# 2um_Homodyne.net
KiCad netlist of a schematic drawn in Altium Designer
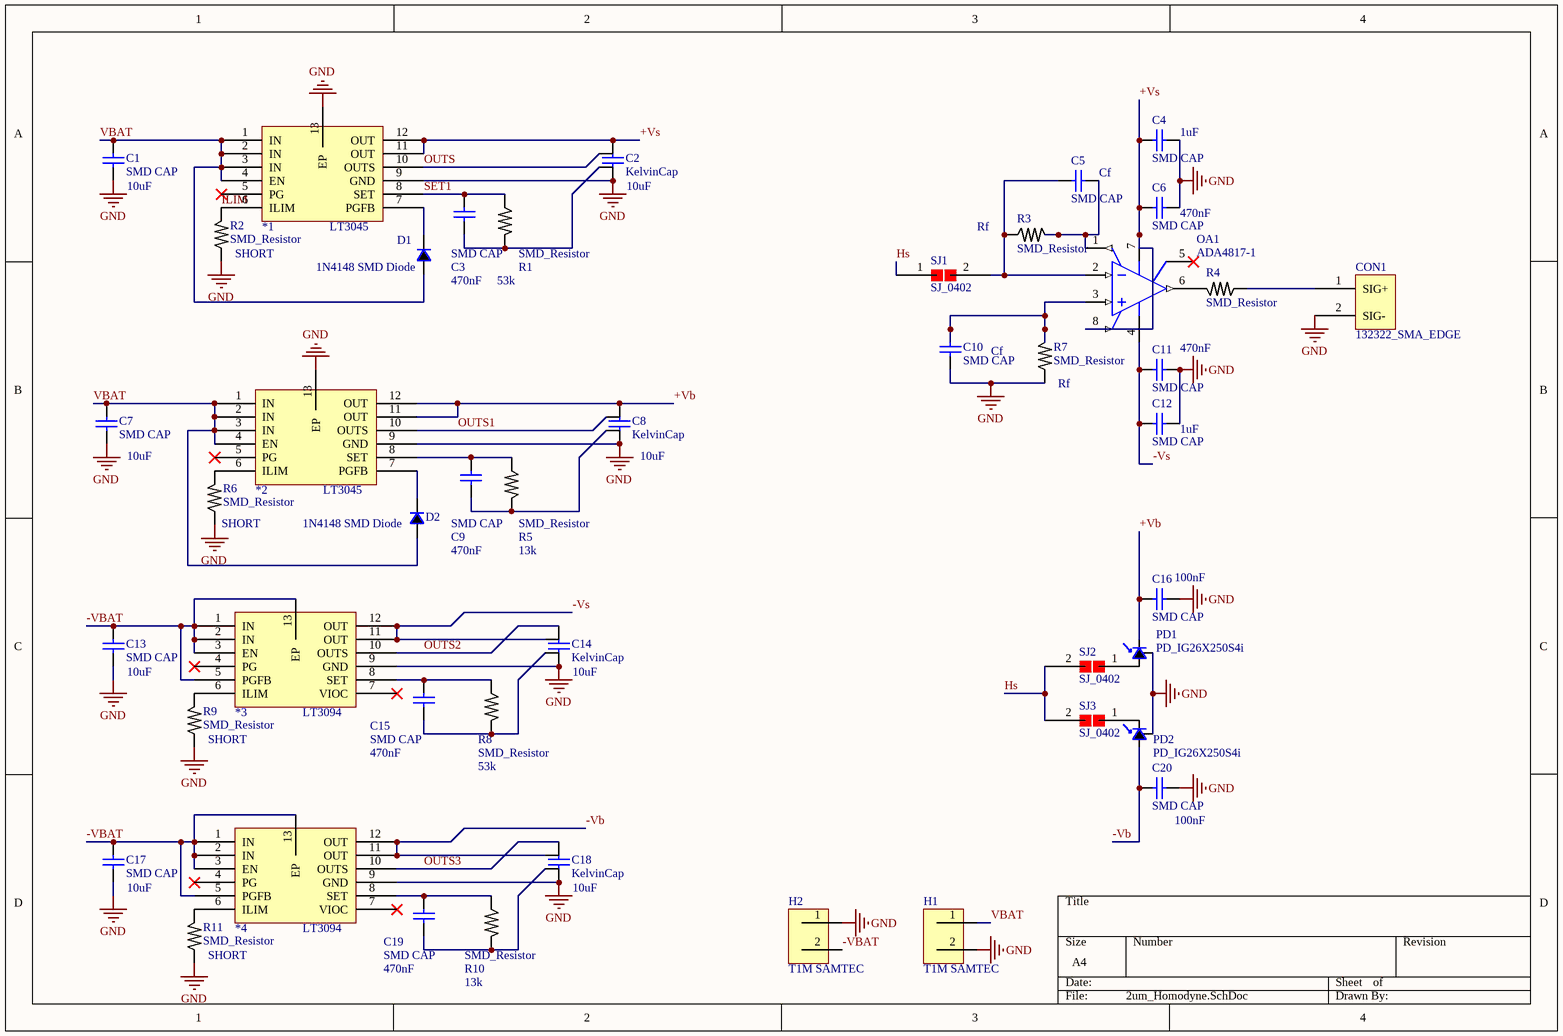
[diagram p0: 2um_Homodyne.SchDoc]

(export (version "E")
  (design (tool "Eeschema 10.0.6"))
  (components
    (comp (ref "*1") (value "LT3045") (footprint "LT3045/3094") (libsource (lib "Homod") (part "LT3045")))
    (comp (ref "*2") (value "LT3045") (footprint "LT3045/3094") (libsource (lib "Homod") (part "LT3045")))
    (comp (ref "*3") (value "LT3094") (footprint "LT3045/3094") (libsource (lib "Homod") (part "LT3094")))
    (comp (ref "*4") (value "LT3094") (footprint "LT3045/3094") (libsource (lib "Homod") (part "LT3094")))
    (comp (ref "C1")
      (value "SMD CAP")
      (footprint "1206CAP")
      (fields (field (name "CAPACITANCE") "10uF"))
      (libsource (lib "Homod") (part "SMD CAP"))
    )
    (comp (ref "C2")
      (value "KelvinCap")
      (footprint "Kelvin1206")
      (fields (field (name "CAPACITANCE") "10uF"))
      (libsource (lib "Homod") (part "KelvinCap"))
    )
    (comp (ref "C3")
      (value "SMD CAP")
      (footprint "0805CAP")
      (fields (field (name "CAPACITANCE") "470nF"))
      (libsource (lib "Homod") (part "SMD CAP"))
    )
    (comp (ref "C4")
      (value "SMD CAP")
      (footprint "0402CAP")
      (fields (field (name "CAPACITANCE") "1uF"))
      (libsource (lib "homod_gen") (part "SMD CAP"))
    )
    (comp (ref "C5")
      (value "SMD CAP")
      (footprint "0402CAP")
      (fields (field (name "FEEDBACK CAPACITANCE") "Cf"))
      (libsource (lib "homod_gen") (part "SMD CAP"))
    )
    (comp (ref "C6")
      (value "SMD CAP")
      (footprint "0402CAP")
      (fields (field (name "CAPACITANCE") "470nF"))
      (libsource (lib "homod_gen") (part "SMD CAP"))
    )
    (comp (ref "C7")
      (value "SMD CAP")
      (footprint "1206CAP")
      (fields (field (name "CAPACITANCE") "10uF"))
      (libsource (lib "Homod") (part "SMD CAP"))
    )
    (comp (ref "C8")
      (value "KelvinCap")
      (footprint "Kelvin1206")
      (fields (field (name "CAPACITANCE") "10uF"))
      (libsource (lib "Homod") (part "KelvinCap"))
    )
    (comp (ref "C9")
      (value "SMD CAP")
      (footprint "0805CAP")
      (fields (field (name "CAPACITANCE") "470nF"))
      (libsource (lib "Homod") (part "SMD CAP"))
    )
    (comp (ref "C10")
      (value "SMD CAP")
      (footprint "0402CAP")
      (fields (field (name "CAPACITANCE") "Cf"))
      (libsource (lib "homod_gen") (part "SMD CAP"))
    )
    (comp (ref "C11")
      (value "SMD CAP")
      (footprint "0402CAP")
      (fields (field (name "CAPACITANCE") "470nF"))
      (libsource (lib "homod_gen") (part "SMD CAP"))
    )
    (comp (ref "C12")
      (value "SMD CAP")
      (footprint "0402CAP")
      (fields (field (name "CAPACITANCE") "1uF"))
      (libsource (lib "homod_gen") (part "SMD CAP"))
    )
    (comp (ref "C13")
      (value "SMD CAP")
      (footprint "1206CAP")
      (fields (field (name "CAPACITANCE") "10uF"))
      (libsource (lib "Homod") (part "SMD CAP"))
    )
    (comp (ref "C14")
      (value "KelvinCap")
      (footprint "Kelvin1206")
      (fields (field (name "CAPACITANCE") "10uF"))
      (libsource (lib "Homod") (part "KelvinCap"))
    )
    (comp (ref "C15")
      (value "SMD CAP")
      (footprint "0805CAP")
      (fields (field (name "CAPACITANCE") "470nF"))
      (libsource (lib "Homod") (part "SMD CAP"))
    )
    (comp (ref "C16")
      (value "SMD CAP")
      (footprint "0402CAP")
      (fields (field (name "CAPACITANCE") "100nF"))
      (libsource (lib "homod_gen") (part "SMD CAP"))
    )
    (comp (ref "C17")
      (value "SMD CAP")
      (footprint "1206CAP")
      (fields (field (name "CAPACITANCE") "10uF"))
      (libsource (lib "Homod") (part "SMD CAP"))
    )
    (comp (ref "C18")
      (value "KelvinCap")
      (footprint "Kelvin1206")
      (fields (field (name "CAPACITANCE") "10uF"))
      (libsource (lib "Homod") (part "KelvinCap"))
    )
    (comp (ref "C19")
      (value "SMD CAP")
      (footprint "0805CAP")
      (fields (field (name "CAPACITANCE") "470nF"))
      (libsource (lib "Homod") (part "SMD CAP"))
    )
    (comp (ref "C20")
      (value "SMD CAP")
      (footprint "0402CAP")
      (fields (field (name "CAPACITANCE") "100nF"))
      (libsource (lib "homod_gen") (part "SMD CAP"))
    )
    (comp (ref "CON1")
      (value "132322_SMA_EDGE")
      (footprint "SMA_EDGE")
      (libsource (lib "homod_gen") (part "132322_SMA_EDGE"))
    )
    (comp (ref "D1")
      (value "1N4148 SMD Diode")
      (footprint "1N4148_SMD DIODE")
      (description "RS: 761-3476")
      (libsource (lib "Homod") (part "1N4148 SMD Diode"))
    )
    (comp (ref "D2")
      (value "1N4148 SMD Diode")
      (footprint "1N4148_SMD DIODE")
      (description "RS: 761-3476")
      (libsource (lib "Homod") (part "1N4148 SMD Diode"))
    )
    (comp (ref "H1")
      (value "T1M SAMTEC")
      (footprint "Mini_Header")
      (libsource (lib "homod_gen") (part "Mini_Header"))
    )
    (comp (ref "H2")
      (value "T1M SAMTEC")
      (footprint "Mini_Header")
      (libsource (lib "homod_gen") (part "Mini_Header"))
    )
    (comp (ref "OA1")
      (value "ADA4817-1")
      (footprint "ADA4817-SOP")
      (libsource (lib "homod_gen") (part "ADA4817-1"))
    )
    (comp (ref "PD1")
      (value "PD_IG26X250S4i")
      (footprint "IG26X250S4i")
      (libsource (lib "homod_gen") (part "PD_IG26X250S4i"))
    )
    (comp (ref "PD2")
      (value "PD_IG26X250S4i")
      (footprint "IG26X250S4i")
      (libsource (lib "homod_gen") (part "PD_IG26X250S4i"))
    )
    (comp (ref "R1")
      (value "SMD_Resistor")
      (footprint "SMD_RES_0402")
      (fields (field (name "RESISTANCE") "53k"))
      (libsource (lib "Homod") (part "SMD_Resistor"))
    )
    (comp (ref "R2")
      (value "SMD_Resistor")
      (footprint "SMD_RES_0402")
      (fields (field (name "RESISTANCE") "SHORT"))
      (libsource (lib "Homod") (part "SMD_Resistor"))
    )
    (comp (ref "R3")
      (value "SMD_Resistor")
      (footprint "SMD_RES_0402")
      (fields (field (name "FEEDBACK RESISTANCE") "Rf"))
      (libsource (lib "homod_gen") (part "SMD_Resistor"))
    )
    (comp (ref "R4")
      (value "SMD_Resistor")
      (footprint "SMD_RES_0402")
      (libsource (lib "homod_gen") (part "SMD_Resistor"))
    )
    (comp (ref "R5")
      (value "SMD_Resistor")
      (footprint "SMD_RES_0402")
      (fields (field (name "RESISTANCCE") "13k"))
      (libsource (lib "Homod") (part "SMD_Resistor"))
    )
    (comp (ref "R6")
      (value "SMD_Resistor")
      (footprint "SMD_RES_0402")
      (fields (field (name "RESISTANACE") "SHORT"))
      (libsource (lib "Homod") (part "SMD_Resistor"))
    )
    (comp (ref "R7")
      (value "SMD_Resistor")
      (footprint "SMD_RES_0402")
      (fields (field (name "RESISTANCE") "Rf"))
      (libsource (lib "homod_gen") (part "SMD_Resistor"))
    )
    (comp (ref "R8")
      (value "SMD_Resistor")
      (footprint "SMD_RES_0402")
      (fields (field (name "RESISTANCE") "53k"))
      (libsource (lib "Homod") (part "SMD_Resistor"))
    )
    (comp (ref "R9")
      (value "SMD_Resistor")
      (footprint "SMD_RES_0402")
      (fields (field (name "RESISTANCE") "SHORT"))
      (libsource (lib "Homod") (part "SMD_Resistor"))
    )
    (comp (ref "R10")
      (value "SMD_Resistor")
      (footprint "SMD_RES_0402")
      (fields (field (name "RESISTANCE") "13k"))
      (libsource (lib "Homod") (part "SMD_Resistor"))
    )
    (comp (ref "R11")
      (value "SMD_Resistor")
      (footprint "SMD_RES_0402")
      (fields (field (name "RESISTANCE") "SHORT"))
      (libsource (lib "Homod") (part "SMD_Resistor"))
    )
    (comp (ref "SJ1")
      (value "SJ_0402")
      (footprint "Solder_Jumper")
      (libsource (lib "homod_gen") (part "SJ_0402"))
    )
    (comp (ref "SJ2") (value "SJ_0402") (footprint "Solder_Jumper") (libsource (lib "") (part "SJ_0402_1")))
    (comp (ref "SJ3") (value "SJ_0402") (footprint "Solder_Jumper") (libsource (lib "") (part "SJ_0402_1")))
  )
  (nets
    (net (code "1") (name "/+Vb") (class "Default")
      (node (ref "*2") (pin "11") (pinfunction "OUT_11") (pintype "power_in"))
      (node (ref "*2") (pin "12") (pinfunction "OUT_12") (pintype "power_in"))
      (node (ref "C16") (pin "1") (pinfunction "1_1") (pintype "passive"))
      (node (ref "C8") (pin "1") (pinfunction "1_1") (pintype "passive"))
      (node (ref "PD1") (pin "3") (pinfunction "Cathode_3") (pintype "power_in"))
    )
    (net (code "2") (name "/+Vs") (class "Default")
      (node (ref "*1") (pin "11") (pinfunction "OUT_11") (pintype "power_in"))
      (node (ref "*1") (pin "12") (pinfunction "OUT_12") (pintype "power_in"))
      (node (ref "C2") (pin "1") (pinfunction "1_1") (pintype "passive"))
      (node (ref "C4") (pin "1") (pinfunction "1_1") (pintype "passive"))
      (node (ref "C6") (pin "1") (pinfunction "1_1") (pintype "passive"))
      (node (ref "OA1") (pin "7") (pinfunction "+VS_7") (pintype "power_in"))
      (node (ref "OA1") (pin "8") (pinfunction "~{PD}_8") (pintype "input"))
    )
    (net (code "3") (name "/-VBAT") (class "Default")
      (node (ref "*3") (pin "1") (pinfunction "IN_1") (pintype "power_in"))
      (node (ref "*3") (pin "13") (pinfunction "EP_13") (pintype "power_in"))
      (node (ref "*3") (pin "2") (pinfunction "IN_2") (pintype "power_in"))
      (node (ref "*3") (pin "3") (pinfunction "EN_3") (pintype "power_in"))
      (node (ref "*3") (pin "5") (pinfunction "PGFB_5") (pintype "power_in"))
      (node (ref "*4") (pin "1") (pinfunction "IN_1") (pintype "power_in"))
      (node (ref "*4") (pin "13") (pinfunction "EP_13") (pintype "power_in"))
      (node (ref "*4") (pin "2") (pinfunction "IN_2") (pintype "power_in"))
      (node (ref "*4") (pin "3") (pinfunction "EN_3") (pintype "power_in"))
      (node (ref "*4") (pin "5") (pinfunction "PGFB_5") (pintype "power_in"))
      (node (ref "C13") (pin "2") (pinfunction "2_2") (pintype "passive"))
      (node (ref "C17") (pin "1") (pinfunction "1_1") (pintype "passive"))
      (node (ref "H2") (pin "2") (pintype "power_in"))
    )
    (net (code "4") (name "/-Vb") (class "Default")
      (node (ref "*4") (pin "11") (pinfunction "OUT_11") (pintype "power_in"))
      (node (ref "*4") (pin "12") (pinfunction "OUT_12") (pintype "power_in"))
      (node (ref "C18") (pin "2") (pinfunction "2_2") (pintype "power_in"))
      (node (ref "C20") (pin "1") (pinfunction "1_1") (pintype "passive"))
      (node (ref "PD2") (pin "1") (pinfunction "Anode_1") (pintype "power_in"))
    )
    (net (code "5") (name "/-Vs") (class "Default")
      (node (ref "*3") (pin "11") (pinfunction "OUT_11") (pintype "power_in"))
      (node (ref "*3") (pin "12") (pinfunction "OUT_12") (pintype "power_in"))
      (node (ref "C11") (pin "1") (pinfunction "1_1") (pintype "passive"))
      (node (ref "C12") (pin "1") (pinfunction "1_1") (pintype "passive"))
      (node (ref "C14") (pin "2") (pinfunction "2_2") (pintype "power_in"))
      (node (ref "OA1") (pin "4") (pinfunction "-VS_4") (pintype "power_in"))
    )
    (net (code "6") (name "/Hs") (class "Default")
      (node (ref "SJ1") (pin "1") (pintype "power_in"))
      (node (ref "SJ2") (pin "2") (pintype "power_in"))
      (node (ref "SJ3") (pin "2") (pintype "power_in"))
    )
    (net (code "7") (name "/ILIM") (class "Default")
      (node (ref "*1") (pin "6") (pinfunction "ILIM_6") (pintype "power_in"))
      (node (ref "R2") (pin "2") (pintype "power_in"))
    )
    (net (code "8") (name "/OUTS") (class "Default")
      (node (ref "*1") (pin "10") (pinfunction "OUTS_10") (pintype "power_in"))
      (node (ref "C2") (pin "2") (pinfunction "2_2") (pintype "power_in"))
    )
    (net (code "9") (name "/OUTS1") (class "Default")
      (node (ref "*2") (pin "10") (pinfunction "OUTS_10") (pintype "power_in"))
      (node (ref "C8") (pin "2") (pinfunction "2_2") (pintype "power_in"))
    )
    (net (code "10") (name "/OUTS2") (class "Default")
      (node (ref "*3") (pin "10") (pinfunction "OUTS_10") (pintype "power_in"))
      (node (ref "C14") (pin "1") (pinfunction "1_1") (pintype "passive"))
    )
    (net (code "11") (name "/OUTS3") (class "Default")
      (node (ref "*4") (pin "10") (pinfunction "OUTS_10") (pintype "power_in"))
      (node (ref "C18") (pin "1") (pinfunction "1_1") (pintype "passive"))
    )
    (net (code "12") (name "/SET1") (class "Default")
      (node (ref "*1") (pin "8") (pinfunction "SET_8") (pintype "power_in"))
      (node (ref "C3") (pin "2") (pinfunction "2_2") (pintype "passive"))
      (node (ref "R1") (pin "1") (pintype "power_in"))
    )
    (net (code "13") (name "/VBAT") (class "Default")
      (node (ref "*1") (pin "1") (pinfunction "IN_1") (pintype "power_in"))
      (node (ref "*1") (pin "2") (pinfunction "IN_2") (pintype "power_in"))
      (node (ref "*1") (pin "3") (pinfunction "IN_3") (pintype "power_in"))
      (node (ref "*1") (pin "4") (pinfunction "EN_4") (pintype "power_in"))
      (node (ref "*2") (pin "1") (pinfunction "IN_1") (pintype "power_in"))
      (node (ref "*2") (pin "2") (pinfunction "IN_2") (pintype "power_in"))
      (node (ref "*2") (pin "3") (pinfunction "IN_3") (pintype "power_in"))
      (node (ref "*2") (pin "4") (pinfunction "EN_4") (pintype "power_in"))
      (node (ref "C1") (pin "2") (pinfunction "2_2") (pintype "passive"))
      (node (ref "C7") (pin "2") (pinfunction "2_2") (pintype "passive"))
      (node (ref "D1") (pin "2") (pinfunction "34_2") (pintype "power_in"))
      (node (ref "D2") (pin "2") (pinfunction "34_2") (pintype "power_in"))
      (node (ref "H1") (pin "1") (pintype "power_in"))
    )
    (net (code "14") (name "GND") (class "Default")
      (node (ref "*1") (pin "13") (pinfunction "EP_13") (pintype "power_in"))
      (node (ref "*1") (pin "9") (pinfunction "GND_9") (pintype "power_in"))
      (node (ref "*2") (pin "13") (pinfunction "EP_13") (pintype "power_in"))
      (node (ref "*2") (pin "9") (pinfunction "GND_9") (pintype "power_in"))
      (node (ref "*3") (pin "9") (pinfunction "GND_9") (pintype "power_in"))
      (node (ref "*4") (pin "9") (pinfunction "GND_9") (pintype "power_in"))
      (node (ref "C1") (pin "1") (pinfunction "1_1") (pintype "passive"))
      (node (ref "C10") (pin "1") (pinfunction "1_1") (pintype "passive"))
      (node (ref "C11") (pin "2") (pinfunction "2_2") (pintype "passive"))
      (node (ref "C12") (pin "2") (pinfunction "2_2") (pintype "passive"))
      (node (ref "C13") (pin "1") (pinfunction "1_1") (pintype "passive"))
      (node (ref "C14") (pin "3") (pinfunction "2_3") (pintype "passive"))
      (node (ref "C16") (pin "2") (pinfunction "2_2") (pintype "passive"))
      (node (ref "C17") (pin "2") (pinfunction "2_2") (pintype "passive"))
      (node (ref "C18") (pin "3") (pinfunction "2_3") (pintype "passive"))
      (node (ref "C2") (pin "3") (pinfunction "2_3") (pintype "passive"))
      (node (ref "C20") (pin "2") (pinfunction "2_2") (pintype "passive"))
      (node (ref "C4") (pin "2") (pinfunction "2_2") (pintype "passive"))
      (node (ref "C6") (pin "2") (pinfunction "2_2") (pintype "passive"))
      (node (ref "C7") (pin "1") (pinfunction "1_1") (pintype "passive"))
      (node (ref "C8") (pin "3") (pinfunction "2_3") (pintype "passive"))
      (node (ref "CON1") (pin "2") (pinfunction "SIG-_2") (pintype "power_in"))
      (node (ref "H1") (pin "2") (pintype "power_in"))
      (node (ref "H2") (pin "1") (pintype "power_in"))
      (node (ref "PD1") (pin "2") (pinfunction "GND/CASE_2") (pintype "power_in"))
      (node (ref "PD2") (pin "2") (pinfunction "GND/CASE_2") (pintype "power_in"))
      (node (ref "R11") (pin "1") (pintype "power_in"))
      (node (ref "R2") (pin "1") (pintype "power_in"))
      (node (ref "R6") (pin "1") (pintype "power_in"))
      (node (ref "R7") (pin "1") (pintype "power_in"))
      (node (ref "R9") (pin "1") (pintype "power_in"))
    )
    (net (code "15") (name "Net-(*1-PGFB)") (class "Default")
      (node (ref "*1") (pin "7") (pinfunction "PGFB_7") (pintype "power_in"))
      (node (ref "D1") (pin "1") (pinfunction "33_1") (pintype "power_in"))
    )
    (net (code "16") (name "Net-(*2-ILIM)") (class "Default")
      (node (ref "*2") (pin "6") (pinfunction "ILIM_6") (pintype "power_in"))
      (node (ref "R6") (pin "2") (pintype "power_in"))
    )
    (net (code "17") (name "Net-(*2-PGFB)") (class "Default")
      (node (ref "*2") (pin "7") (pinfunction "PGFB_7") (pintype "power_in"))
      (node (ref "D2") (pin "1") (pinfunction "33_1") (pintype "power_in"))
    )
    (net (code "18") (name "Net-(*2-SET)") (class "Default")
      (node (ref "*2") (pin "8") (pinfunction "SET_8") (pintype "power_in"))
      (node (ref "C9") (pin "2") (pinfunction "2_2") (pintype "passive"))
      (node (ref "R5") (pin "1") (pintype "power_in"))
    )
    (net (code "19") (name "Net-(*3-ILIM)") (class "Default")
      (node (ref "*3") (pin "6") (pinfunction "ILIM_6") (pintype "power_in"))
      (node (ref "R9") (pin "2") (pintype "power_in"))
    )
    (net (code "20") (name "Net-(*3-SET)") (class "Default")
      (node (ref "*3") (pin "8") (pinfunction "SET_8") (pintype "power_in"))
      (node (ref "C15") (pin "2") (pinfunction "2_2") (pintype "passive"))
      (node (ref "R8") (pin "1") (pintype "power_in"))
    )
    (net (code "21") (name "Net-(*4-ILIM)") (class "Default")
      (node (ref "*4") (pin "6") (pinfunction "ILIM_6") (pintype "power_in"))
      (node (ref "R11") (pin "2") (pintype "power_in"))
    )
    (net (code "22") (name "Net-(*4-SET)") (class "Default")
      (node (ref "*4") (pin "8") (pinfunction "SET_8") (pintype "power_in"))
      (node (ref "C19") (pin "2") (pinfunction "2_2") (pintype "passive"))
      (node (ref "R10") (pin "1") (pintype "power_in"))
    )
    (net (code "23") (name "Net-(C2-Pad4)") (class "Default")
      (node (ref "C2") (pin "4") (pinfunction "4_4") (pintype "power_in"))
      (node (ref "C3") (pin "1") (pinfunction "1_1") (pintype "passive"))
      (node (ref "R1") (pin "2") (pintype "power_in"))
    )
    (net (code "24") (name "Net-(C8-Pad4)") (class "Default")
      (node (ref "C8") (pin "4") (pinfunction "4_4") (pintype "power_in"))
      (node (ref "C9") (pin "1") (pinfunction "1_1") (pintype "passive"))
      (node (ref "R5") (pin "2") (pintype "power_in"))
    )
    (net (code "25") (name "Net-(C14-Pad4)") (class "Default")
      (node (ref "C14") (pin "4") (pinfunction "4_4") (pintype "power_in"))
      (node (ref "C15") (pin "1") (pinfunction "1_1") (pintype "passive"))
      (node (ref "R8") (pin "2") (pintype "power_in"))
    )
    (net (code "26") (name "Net-(C18-Pad4)") (class "Default")
      (node (ref "C18") (pin "4") (pinfunction "4_4") (pintype "power_in"))
      (node (ref "C19") (pin "1") (pinfunction "1_1") (pintype "passive"))
      (node (ref "R10") (pin "2") (pintype "power_in"))
    )
    (net (code "27") (name "Net-(CON1-SIG+)") (class "Default")
      (node (ref "CON1") (pin "1") (pinfunction "SIG+_1") (pintype "power_in"))
      (node (ref "R4") (pin "1") (pintype "power_in"))
    )
    (net (code "28") (name "Net-(OA1-+IN)") (class "Default")
      (node (ref "C10") (pin "2") (pinfunction "2_2") (pintype "passive"))
      (node (ref "OA1") (pin "3") (pinfunction "+IN_3") (pintype "input"))
      (node (ref "R7") (pin "2") (pintype "power_in"))
    )
    (net (code "29") (name "Net-(OA1--IN)") (class "Default")
      (node (ref "C5") (pin "1") (pinfunction "1_1") (pintype "passive"))
      (node (ref "OA1") (pin "2") (pinfunction "-IN_2") (pintype "input"))
      (node (ref "R3") (pin "1") (pintype "power_in"))
      (node (ref "SJ1") (pin "2") (pintype "power_in"))
    )
    (net (code "30") (name "Net-(OA1-FB)") (class "Default")
      (node (ref "C5") (pin "2") (pinfunction "2_2") (pintype "passive"))
      (node (ref "OA1") (pin "1") (pinfunction "FB_1") (pintype "output"))
      (node (ref "R3") (pin "2") (pintype "power_in"))
    )
    (net (code "31") (name "Net-(OA1-OUT)") (class "Default")
      (node (ref "OA1") (pin "6") (pinfunction "OUT_6") (pintype "output"))
      (node (ref "R4") (pin "2") (pintype "power_in"))
    )
    (net (code "32") (name "Net-(PD1-Anode)") (class "Default")
      (node (ref "PD1") (pin "1") (pinfunction "Anode_1") (pintype "power_in"))
      (node (ref "SJ2") (pin "1") (pintype "power_in"))
    )
    (net (code "33") (name "Net-(PD2-Cathode)") (class "Default")
      (node (ref "PD2") (pin "3") (pinfunction "Cathode_3") (pintype "power_in"))
      (node (ref "SJ3") (pin "1") (pintype "power_in"))
    )
    (net (code "34") (name "unconnected-(*1-PG-Pad5)") (class "Default")
      (node (ref "*1") (pin "5") (pinfunction "PG_5") (pintype "power_in+no_connect"))
    )
    (net (code "35") (name "unconnected-(*2-PG-Pad5)") (class "Default")
      (node (ref "*2") (pin "5") (pinfunction "PG_5") (pintype "power_in+no_connect"))
    )
    (net (code "36") (name "unconnected-(*3-PG-Pad4)") (class "Default")
      (node (ref "*3") (pin "4") (pinfunction "PG_4") (pintype "power_in+no_connect"))
    )
    (net (code "37") (name "unconnected-(*3-VIOC-Pad7)") (class "Default")
      (node (ref "*3") (pin "7") (pinfunction "VIOC_7") (pintype "power_in+no_connect"))
    )
    (net (code "38") (name "unconnected-(*4-PG-Pad4)") (class "Default")
      (node (ref "*4") (pin "4") (pinfunction "PG_4") (pintype "power_in+no_connect"))
    )
    (net (code "39") (name "unconnected-(*4-VIOC-Pad7)") (class "Default")
      (node (ref "*4") (pin "7") (pinfunction "VIOC_7") (pintype "power_in+no_connect"))
    )
    (net (code "40") (name "unconnected-(OA1-NC-Pad5)") (class "Default")
      (node (ref "OA1") (pin "5") (pinfunction "NC_5") (pintype "passive+no_connect"))
    )
  )
)
